# sch_USB3_0.net
KiCad netlist of a schematic drawn in Altium Designer
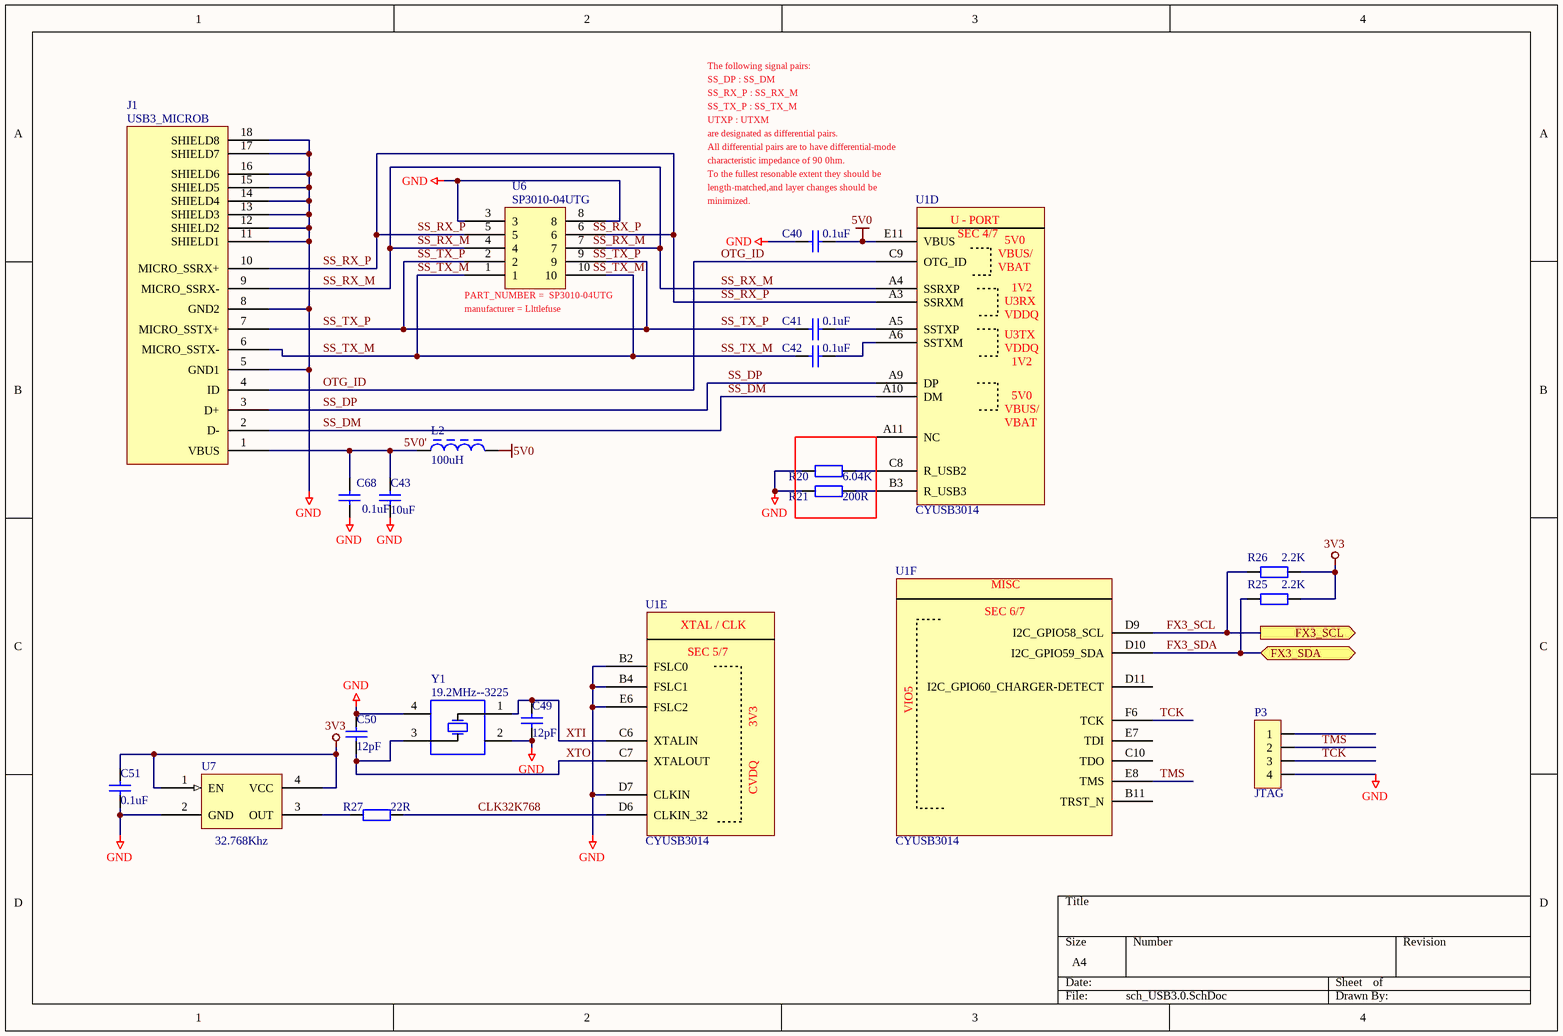
[diagram p0: sch_USB3.0.SchDoc]

(export (version "E")
  (design (tool "Eeschema 10.0.6"))
  (components
    (comp (ref "C40")
      (value "0.1uF")
      (footprint "0402C")
      (description "Capacitor")
      (fields (field (name "PUBLISHER") "Altium Limited"))
      (libsource (lib "Miscellaneous Devices") (part "Cap"))
    )
    (comp (ref "C41")
      (value "0.1uF")
      (footprint "0402C")
      (description "Capacitor")
      (fields (field (name "PUBLISHER") "Altium Limited"))
      (libsource (lib "Miscellaneous Devices") (part "Cap"))
    )
    (comp (ref "C42")
      (value "0.1uF")
      (footprint "0402C")
      (description "Capacitor")
      (fields (field (name "PUBLISHER") "Altium Limited"))
      (libsource (lib "Miscellaneous Devices") (part "Cap"))
    )
    (comp (ref "C43")
      (value "10uF")
      (footprint "0805C")
      (description "Capacitor")
      (fields (field (name "PUBLISHER") "Altium Limited"))
      (libsource (lib "Miscellaneous Devices") (part "Cap"))
    )
    (comp (ref "C49")
      (value "12pF")
      (footprint "0402C")
      (description "Capacitor")
      (fields (field (name "PUBLISHER") "Altium Limited"))
      (libsource (lib "Miscellaneous Devices") (part "Cap"))
    )
    (comp (ref "C50")
      (value "12pF")
      (footprint "0402C")
      (description "Capacitor")
      (fields (field (name "PUBLISHER") "Altium Limited"))
      (libsource (lib "Miscellaneous Devices") (part "Cap"))
    )
    (comp (ref "C51")
      (value "0.1uF")
      (footprint "0402C")
      (description "Capacitor")
      (fields (field (name "PUBLISHER") "Altium Limited"))
      (libsource (lib "Miscellaneous Devices") (part "Cap"))
    )
    (comp (ref "C68")
      (value "0.1uF")
      (footprint "0402C")
      (description "Capacitor")
      (fields (field (name "PUBLISHER") "Altium Limited"))
      (libsource (lib "Miscellaneous Devices") (part "Cap"))
    )
    (comp (ref "J1")
      (value "USB3_MICROB")
      (footprint "USB3_BA_P65L130W51H28")
      (libsource (lib "SZG") (part "USB3_MICROB"))
    )
    (comp (ref "L2")
      (value "100uH")
      (footprint "L_P3D6H9")
      (description "7.2.04.0034 立式电感受10uH 2A")
      (libsource (lib "*") (part "L"))
    )
    (comp (ref "P3")
      (value "JTAG")
      (footprint "WAFER4_P1.25L6.25W3.4H4.3")
      (libsource (lib "KS_Drive") (part "CON4"))
    )
    (comp (ref "R20")
      (value "6.04K")
      (footprint "0402R")
      (description "Resistor")
      (fields (field (name "PUBLISHER") "Altium Limited"))
      (libsource (lib "SZG") (part "Resistor"))
    )
    (comp (ref "R21")
      (value "200R")
      (footprint "0402R")
      (description "Resistor")
      (fields (field (name "PUBLISHER") "Altium Limited"))
      (libsource (lib "SZG") (part "Resistor"))
    )
    (comp (ref "R25")
      (value "2.2K")
      (footprint "0402R")
      (description "Resistor")
      (fields (field (name "PUBLISHER") "Altium Limited"))
      (libsource (lib "SZG") (part "Resistor"))
    )
    (comp (ref "R26")
      (value "2.2K")
      (footprint "0402R")
      (description "Resistor")
      (fields (field (name "PUBLISHER") "Altium Limited"))
      (libsource (lib "SZG") (part "Resistor"))
    )
    (comp (ref "R27")
      (value "22R")
      (footprint "0402R")
      (description "Resistor")
      (fields (field (name "PUBLISHER") "Altium Limited"))
      (libsource (lib "SZG") (part "Resistor"))
    )
    (comp (ref "U1")
      (value "CYUSB3014")
      (footprint "FBGA121_P80L100W100H11")
      (libsource (lib "TXW") (part "CYUSB3014"))
    )
    (comp (ref "U6")
      (value "SP3010-04UTG")
      (footprint "UDFN10_SON_P50L25W10H55")
      (libsource (lib "SZG") (part "SP3010-04UTG"))
    )
    (comp (ref "U7")
      (value "XTAL-3225")
      (footprint "XTAL_3225")
      (libsource (lib "常用晶振器件图SCH") (part "XTAL."))
    )
    (comp (ref "Y1")
      (value "19.2MHz--3225")
      (footprint "XTAL_3225")
      (description "Crystal Oscillator")
      (libsource (lib "常用晶振器件图SCH") (part "XTAL"))
    )
  )
  (nets
    (net (code "1") (name "/5V0'") (class "Default")
      (node (ref "C43") (pin "2") (pinfunction "2_2") (pintype "passive"))
      (node (ref "C68") (pin "1") (pinfunction "1_1") (pintype "passive"))
      (node (ref "J1") (pin "1") (pinfunction "VBUS_1") (pintype "power_in"))
      (node (ref "L2") (pin "1") (pintype "passive"))
    )
    (net (code "2") (name "/CLK32K768") (class "Default")
      (node (ref "R27") (pin "1") (pinfunction "1_1") (pintype "passive"))
      (node (ref "U1") (pin "D6") (pinfunction "CLKIN_32_D6") (pintype "passive"))
    )
    (net (code "3") (name "/FX3_SCL") (class "Default")
      (node (ref "R26") (pin "2") (pinfunction "2_2") (pintype "passive"))
      (node (ref "U1") (pin "D9") (pinfunction "I2C_GPIO58_SCL_D9") (pintype "passive"))
    )
    (net (code "4") (name "/FX3_SDA") (class "Default")
      (node (ref "R25") (pin "2") (pinfunction "2_2") (pintype "passive"))
      (node (ref "U1") (pin "D10") (pinfunction "I2C_GPIO59_SDA_D10") (pintype "passive"))
    )
    (net (code "5") (name "/OTG_ID") (class "Default")
      (node (ref "J1") (pin "4") (pinfunction "ID_4") (pintype "power_in"))
      (node (ref "U1") (pin "C9") (pinfunction "OTG_ID_C9") (pintype "power_in"))
    )
    (net (code "6") (name "/SS_DM") (class "Default")
      (node (ref "J1") (pin "2") (pinfunction "D-_2") (pintype "power_in"))
      (node (ref "U1") (pin "A10") (pinfunction "DM_A10") (pintype "power_in"))
    )
    (net (code "7") (name "/SS_DP") (class "Default")
      (node (ref "J1") (pin "3") (pinfunction "D+_3") (pintype "power_in"))
      (node (ref "U1") (pin "A9") (pinfunction "DP_A9") (pintype "power_in"))
    )
    (net (code "8") (name "/SS_RX_M") (class "Default")
      (node (ref "J1") (pin "9") (pinfunction "MICRO_SSRX-_9") (pintype "power_in"))
      (node (ref "U1") (pin "A4") (pinfunction "SSRXP_A4") (pintype "power_in"))
      (node (ref "U6") (pin "4") (pinfunction "4_4") (pintype "passive"))
      (node (ref "U6") (pin "7") (pinfunction "7_7") (pintype "passive"))
    )
    (net (code "9") (name "/SS_RX_P") (class "Default")
      (node (ref "J1") (pin "10") (pinfunction "MICRO_SSRX+_10") (pintype "power_in"))
      (node (ref "U1") (pin "A3") (pinfunction "SSRXM_A3") (pintype "power_in"))
      (node (ref "U6") (pin "5") (pinfunction "5_5") (pintype "passive"))
      (node (ref "U6") (pin "6") (pinfunction "6_6") (pintype "passive"))
    )
    (net (code "10") (name "/SS_TX_M") (class "Default")
      (node (ref "C42") (pin "2") (pinfunction "2_2") (pintype "passive"))
      (node (ref "J1") (pin "6") (pinfunction "MICRO_SSTX-_6") (pintype "power_in"))
      (node (ref "U6") (pin "1") (pinfunction "1_1") (pintype "passive"))
      (node (ref "U6") (pin "10") (pinfunction "10_10") (pintype "passive"))
    )
    (net (code "11") (name "/SS_TX_P") (class "Default")
      (node (ref "C41") (pin "2") (pinfunction "2_2") (pintype "passive"))
      (node (ref "J1") (pin "7") (pinfunction "MICRO_SSTX+_7") (pintype "power_in"))
      (node (ref "U6") (pin "2") (pinfunction "2_2") (pintype "passive"))
      (node (ref "U6") (pin "9") (pinfunction "9_9") (pintype "passive"))
    )
    (net (code "12") (name "/TCK") (class "Default")
      (node (ref "P3") (pin "3") (pinfunction "3_3") (pintype "passive"))
      (node (ref "U1") (pin "F6") (pinfunction "TCK_F6") (pintype "passive"))
    )
    (net (code "13") (name "/TMS") (class "Default")
      (node (ref "P3") (pin "2") (pinfunction "2_2") (pintype "passive"))
      (node (ref "U1") (pin "E8") (pinfunction "TMS_E8") (pintype "passive"))
    )
    (net (code "14") (name "/XTI") (class "Default")
      (node (ref "C49") (pin "2") (pinfunction "2_2") (pintype "passive"))
      (node (ref "U1") (pin "C6") (pinfunction "XTALIN_C6") (pintype "passive"))
      (node (ref "Y1") (pin "1") (pinfunction "1_1") (pintype "passive"))
    )
    (net (code "15") (name "/XTO") (class "Default")
      (node (ref "C50") (pin "1") (pinfunction "1_1") (pintype "passive"))
      (node (ref "U1") (pin "C7") (pinfunction "XTALOUT_C7") (pintype "passive"))
      (node (ref "Y1") (pin "3") (pinfunction "3_3") (pintype "passive"))
    )
    (net (code "16") (name "3V3") (class "Default")
      (node (ref "C51") (pin "2") (pinfunction "2_2") (pintype "passive"))
      (node (ref "R25") (pin "1") (pinfunction "1_1") (pintype "passive"))
      (node (ref "R26") (pin "1") (pinfunction "1_1") (pintype "passive"))
      (node (ref "U7") (pin "1") (pinfunction "EN_1") (pintype "input"))
      (node (ref "U7") (pin "4") (pinfunction "VCC_4") (pintype "passive"))
    )
    (net (code "17") (name "5V0") (class "Default")
      (node (ref "C40") (pin "1") (pinfunction "1_1") (pintype "passive"))
      (node (ref "L2") (pin "2") (pintype "passive"))
      (node (ref "U1") (pin "E11") (pinfunction "VBUS_E11") (pintype "power_in"))
    )
    (net (code "18") (name "GND") (class "Default")
      (node (ref "C40") (pin "2") (pinfunction "2_2") (pintype "passive"))
      (node (ref "C43") (pin "1") (pinfunction "1_1") (pintype "passive"))
      (node (ref "C49") (pin "1") (pinfunction "1_1") (pintype "passive"))
      (node (ref "C50") (pin "2") (pinfunction "2_2") (pintype "passive"))
      (node (ref "C51") (pin "1") (pinfunction "1_1") (pintype "passive"))
      (node (ref "C68") (pin "2") (pinfunction "2_2") (pintype "passive"))
      (node (ref "J1") (pin "11") (pinfunction "SHIELD1_11") (pintype "power_in"))
      (node (ref "J1") (pin "12") (pinfunction "SHIELD2_12") (pintype "power_in"))
      (node (ref "J1") (pin "13") (pinfunction "SHIELD3_13") (pintype "power_in"))
      (node (ref "J1") (pin "14") (pinfunction "SHIELD4_14") (pintype "power_in"))
      (node (ref "J1") (pin "15") (pinfunction "SHIELD5_15") (pintype "power_in"))
      (node (ref "J1") (pin "16") (pinfunction "SHIELD6_16") (pintype "power_in"))
      (node (ref "J1") (pin "17") (pinfunction "SHIELD7_17") (pintype "power_in"))
      (node (ref "J1") (pin "18") (pinfunction "SHIELD8_18") (pintype "power_in"))
      (node (ref "J1") (pin "5") (pinfunction "GND1_5") (pintype "power_in"))
      (node (ref "J1") (pin "8") (pinfunction "GND2_8") (pintype "power_in"))
      (node (ref "P3") (pin "4") (pinfunction "4_4") (pintype "passive"))
      (node (ref "R20") (pin "2") (pinfunction "2_2") (pintype "passive"))
      (node (ref "R21") (pin "2") (pinfunction "2_2") (pintype "passive"))
      (node (ref "U1") (pin "B2") (pinfunction "FSLC0_B2") (pintype "passive"))
      (node (ref "U1") (pin "B4") (pinfunction "FSLC1_B4") (pintype "passive"))
      (node (ref "U1") (pin "D7") (pinfunction "CLKIN_D7") (pintype "passive"))
      (node (ref "U1") (pin "E6") (pinfunction "FSLC2_E6") (pintype "passive"))
      (node (ref "U6") (pin "3") (pinfunction "3_3") (pintype "passive"))
      (node (ref "U6") (pin "8") (pinfunction "8_8") (pintype "passive"))
      (node (ref "U7") (pin "2") (pinfunction "GND_2") (pintype "passive"))
      (node (ref "Y1") (pin "2") (pinfunction "2_2") (pintype "passive"))
      (node (ref "Y1") (pin "4") (pinfunction "4_4") (pintype "passive"))
    )
    (net (code "19") (name "Net-(U1D-R_USB2)") (class "Default")
      (node (ref "R20") (pin "1") (pinfunction "1_1") (pintype "passive"))
      (node (ref "U1") (pin "C8") (pinfunction "R_USB2_C8") (pintype "power_in"))
    )
    (net (code "20") (name "Net-(U1D-R_USB3)") (class "Default")
      (node (ref "R21") (pin "1") (pinfunction "1_1") (pintype "passive"))
      (node (ref "U1") (pin "B3") (pinfunction "R_USB3_B3") (pintype "power_in"))
    )
    (net (code "21") (name "Net-(U1D-SSTXM)") (class "Default")
      (node (ref "C42") (pin "1") (pinfunction "1_1") (pintype "passive"))
      (node (ref "U1") (pin "A6") (pinfunction "SSTXM_A6") (pintype "power_in"))
    )
    (net (code "22") (name "Net-(U1D-SSTXP)") (class "Default")
      (node (ref "C41") (pin "1") (pinfunction "1_1") (pintype "passive"))
      (node (ref "U1") (pin "A5") (pinfunction "SSTXP_A5") (pintype "power_in"))
    )
    (net (code "23") (name "Net-(U7-OUT)") (class "Default")
      (node (ref "R27") (pin "2") (pinfunction "2_2") (pintype "passive"))
      (node (ref "U7") (pin "3") (pinfunction "OUT_3") (pintype "passive"))
    )
    (net (code "24") (name "unconnected-(P3-Pad1)") (class "Default")
      (node (ref "P3") (pin "1") (pinfunction "1_1") (pintype "passive"))
    )
    (net (code "25") (name "unconnected-(U1D-NC-PadA11)") (class "Default")
      (node (ref "U1") (pin "A11") (pinfunction "NC_A11") (pintype "power_in"))
    )
    (net (code "26") (name "unconnected-(U1F-I2C_GPIO60_CHARGER-DETECT-PadD11)") (class "Default")
      (node (ref "U1") (pin "D11") (pinfunction "I2C_GPIO60_CHARGER-DETECT_D11") (pintype "passive"))
    )
    (net (code "27") (name "unconnected-(U1F-TDI-PadE7)") (class "Default")
      (node (ref "U1") (pin "E7") (pinfunction "TDI_E7") (pintype "passive"))
    )
    (net (code "28") (name "unconnected-(U1F-TDO-PadC10)") (class "Default")
      (node (ref "U1") (pin "C10") (pinfunction "TDO_C10") (pintype "passive"))
    )
    (net (code "29") (name "unconnected-(U1F-TRST_N-PadB11)") (class "Default")
      (node (ref "U1") (pin "B11") (pinfunction "TRST_N_B11") (pintype "passive"))
    )
  )
)
